# Ad8232_placa_V3_SPlanoTerra.net
KiCad netlist of a schematic drawn in EAGLE
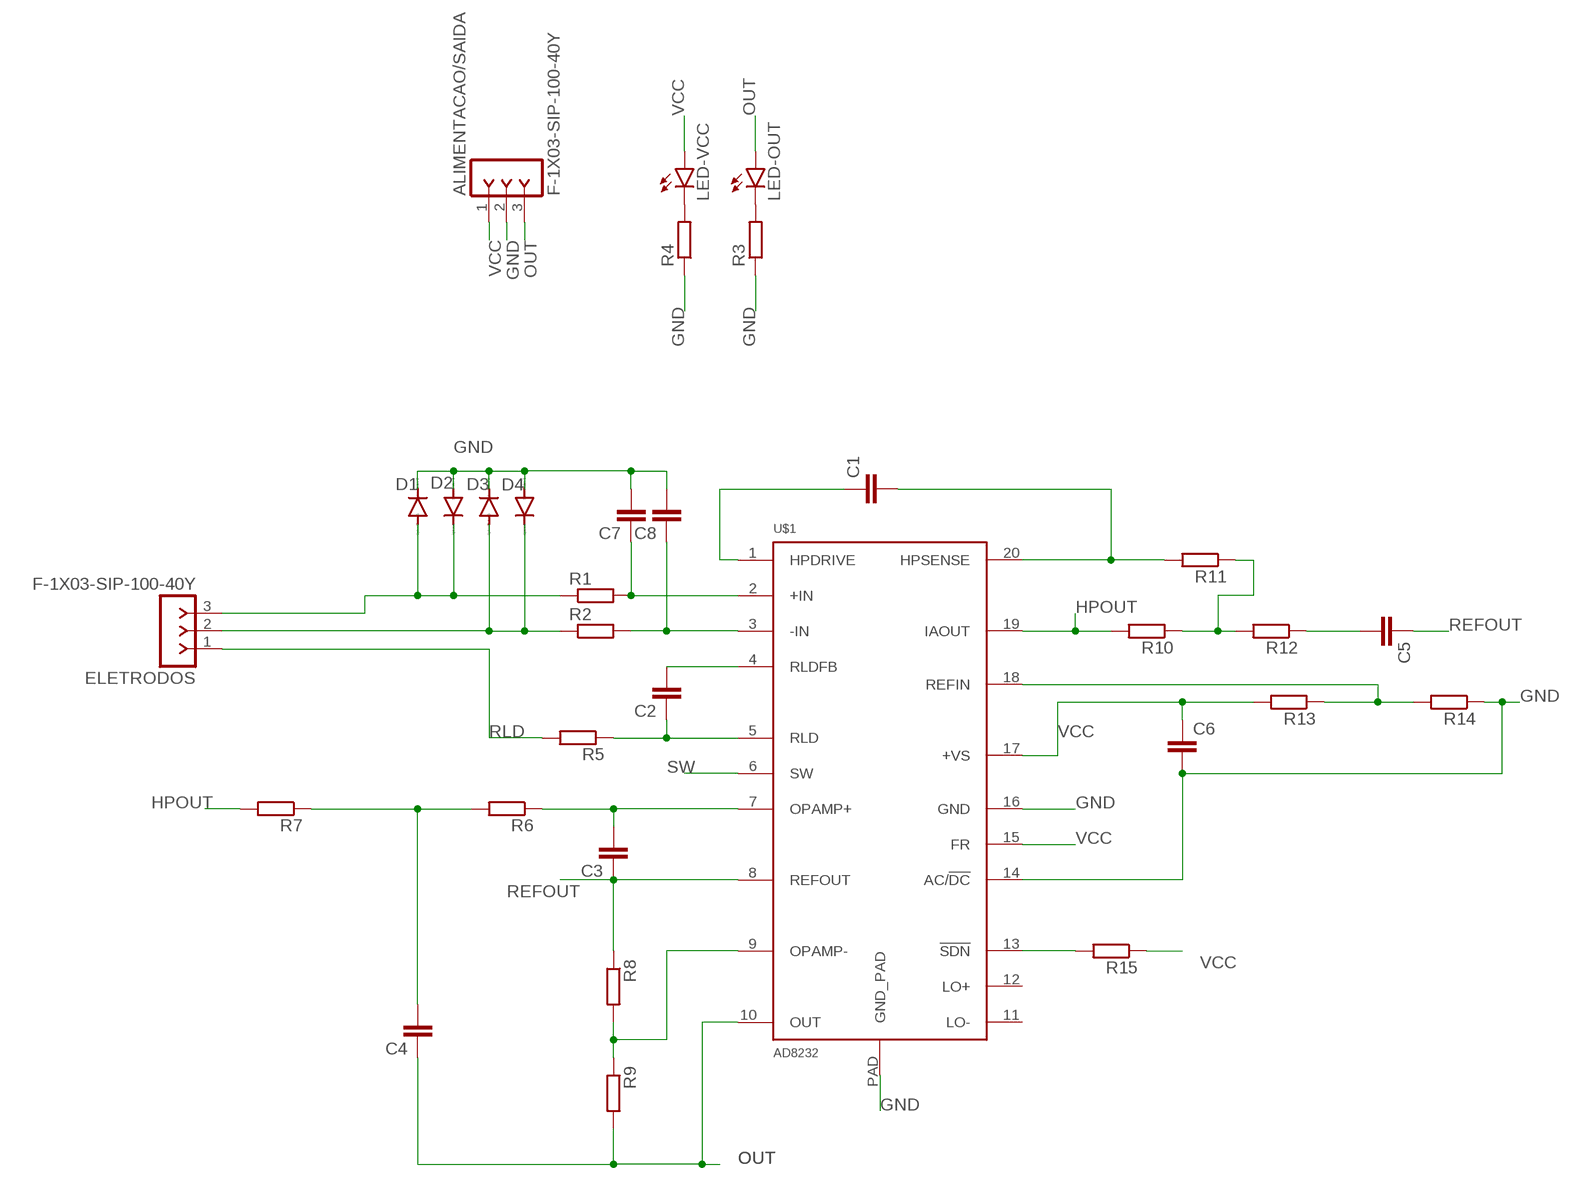
[diagram p0: schematic, sheet 1]

(export (version "E")
  (design (tool "Eeschema 10.0.6"))
  (components
    (comp (ref "ALIMENTACAO/SAIDA")
      (value "F-1X03-SIP-100-40Y")
      (footprint "eagle-import:SIP-100-03-40Y")
      (libsource (lib "eagle-import") (part "F-1X03-SIP-100-40Y"))
    )
    (comp (ref "C1")
      (value "C-EUC0805")
      (footprint "eagle-import:C0805")
      (libsource (lib "eagle-import") (part "C-EUC0805"))
    )
    (comp (ref "C2")
      (value "C-EUC0805")
      (footprint "eagle-import:C0805")
      (libsource (lib "eagle-import") (part "C-EUC0805"))
    )
    (comp (ref "C3")
      (value "C-EUC0805")
      (footprint "eagle-import:C0805")
      (libsource (lib "eagle-import") (part "C-EUC0805"))
    )
    (comp (ref "C4")
      (value "C-EUC0805")
      (footprint "eagle-import:C0805")
      (libsource (lib "eagle-import") (part "C-EUC0805"))
    )
    (comp (ref "C5")
      (value "C-EUC0805")
      (footprint "eagle-import:C0805")
      (libsource (lib "eagle-import") (part "C-EUC0805"))
    )
    (comp (ref "C6")
      (value "C-EUC0805")
      (footprint "eagle-import:C0805")
      (libsource (lib "eagle-import") (part "C-EUC0805"))
    )
    (comp (ref "C7")
      (value "C-EUC0805")
      (footprint "eagle-import:C0805")
      (libsource (lib "eagle-import") (part "C-EUC0805"))
    )
    (comp (ref "C8")
      (value "C-EUC0805")
      (footprint "eagle-import:C0805")
      (libsource (lib "eagle-import") (part "C-EUC0805"))
    )
    (comp (ref "D1")
      (value "DIODE-MINIMELF")
      (footprint "eagle-import:MINIMELF")
      (libsource (lib "eagle-import") (part "DIODE-MINIMELF"))
    )
    (comp (ref "D2")
      (value "DIODE-MINIMELF")
      (footprint "eagle-import:MINIMELF")
      (libsource (lib "eagle-import") (part "DIODE-MINIMELF"))
    )
    (comp (ref "D3")
      (value "DIODE-MINIMELF")
      (footprint "eagle-import:MINIMELF")
      (libsource (lib "eagle-import") (part "DIODE-MINIMELF"))
    )
    (comp (ref "D4")
      (value "DIODE-MINIMELF")
      (footprint "eagle-import:MINIMELF")
      (libsource (lib "eagle-import") (part "DIODE-MINIMELF"))
    )
    (comp (ref "ELETRODOS")
      (value "F-1X03-SIP-100-40Y")
      (footprint "eagle-import:SIP-100-03-40Y")
      (libsource (lib "eagle-import") (part "F-1X03-SIP-100-40Y"))
    )
    (comp (ref "LED-OUT")
      (value "LEDCHIPLED_0603")
      (footprint "eagle-import:CHIPLED_0603")
      (libsource (lib "eagle-import") (part "LEDCHIPLED_0603"))
    )
    (comp (ref "LED-VCC")
      (value "LEDCHIPLED_0603")
      (footprint "eagle-import:CHIPLED_0603")
      (libsource (lib "eagle-import") (part "LEDCHIPLED_0603"))
    )
    (comp (ref "R1")
      (value "R-EU_R0805")
      (footprint "eagle-import:R0805")
      (libsource (lib "eagle-import") (part "R-EU_R0805"))
    )
    (comp (ref "R2")
      (value "R-EU_R0805")
      (footprint "eagle-import:R0805")
      (libsource (lib "eagle-import") (part "R-EU_R0805"))
    )
    (comp (ref "R3")
      (value "R-EU_R0805")
      (footprint "eagle-import:R0805")
      (libsource (lib "eagle-import") (part "R-EU_R0805"))
    )
    (comp (ref "R4")
      (value "R-EU_R0805")
      (footprint "eagle-import:R0805")
      (libsource (lib "eagle-import") (part "R-EU_R0805"))
    )
    (comp (ref "R5")
      (value "R-EU_R0805")
      (footprint "eagle-import:R0805")
      (libsource (lib "eagle-import") (part "R-EU_R0805"))
    )
    (comp (ref "R6")
      (value "R-EU_R0805")
      (footprint "eagle-import:R0805")
      (libsource (lib "eagle-import") (part "R-EU_R0805"))
    )
    (comp (ref "R7")
      (value "R-EU_R0805")
      (footprint "eagle-import:R0805")
      (libsource (lib "eagle-import") (part "R-EU_R0805"))
    )
    (comp (ref "R8")
      (value "R-EU_R0805")
      (footprint "eagle-import:R0805")
      (libsource (lib "eagle-import") (part "R-EU_R0805"))
    )
    (comp (ref "R9")
      (value "R-EU_R0805")
      (footprint "eagle-import:R0805")
      (libsource (lib "eagle-import") (part "R-EU_R0805"))
    )
    (comp (ref "R10")
      (value "R-EU_R0805")
      (footprint "eagle-import:R0805")
      (libsource (lib "eagle-import") (part "R-EU_R0805"))
    )
    (comp (ref "R11")
      (value "R-EU_R0805")
      (footprint "eagle-import:R0805")
      (libsource (lib "eagle-import") (part "R-EU_R0805"))
    )
    (comp (ref "R12")
      (value "R-EU_R0805")
      (footprint "eagle-import:R0805")
      (libsource (lib "eagle-import") (part "R-EU_R0805"))
    )
    (comp (ref "R13")
      (value "R-EU_R0805")
      (footprint "eagle-import:R0805")
      (libsource (lib "eagle-import") (part "R-EU_R0805"))
    )
    (comp (ref "R14")
      (value "R-EU_R0805")
      (footprint "eagle-import:R0805")
      (libsource (lib "eagle-import") (part "R-EU_R0805"))
    )
    (comp (ref "R15")
      (value "R-EU_R0805")
      (footprint "eagle-import:R0805")
      (libsource (lib "eagle-import") (part "R-EU_R0805"))
    )
    (comp (ref "U$1")
      (value "AD8232")
      (footprint "eagle-import:LFCSP_20")
      (fields (field (name "MF") "Analog Devices"))
      (libsource (lib "eagle-import") (part "AD8232"))
    )
  )
  (nets
    (net (code "1") (name "/GND") (class "Default")
      (node (ref "ALIMENTACAO/SAIDA") (pin "2") (pinfunction "2_2") (pintype "passive"))
      (node (ref "C6") (pin "2") (pinfunction "2_2") (pintype "passive"))
      (node (ref "C7") (pin "2") (pinfunction "2_2") (pintype "passive"))
      (node (ref "C8") (pin "2") (pinfunction "2_2") (pintype "passive"))
      (node (ref "D1") (pin "C") (pinfunction "C_C") (pintype "passive"))
      (node (ref "D2") (pin "A") (pinfunction "A_A") (pintype "passive"))
      (node (ref "D3") (pin "C") (pinfunction "C_C") (pintype "passive"))
      (node (ref "D4") (pin "A") (pinfunction "A_A") (pintype "passive"))
      (node (ref "R14") (pin "1") (pinfunction "1_1") (pintype "passive"))
      (node (ref "R3") (pin "1") (pinfunction "1_1") (pintype "passive"))
      (node (ref "R4") (pin "1") (pinfunction "1_1") (pintype "passive"))
      (node (ref "U$1") (pin "14") (pinfunction "AC/~{DC}_14") (pintype "bidirectional"))
      (node (ref "U$1") (pin "16") (pinfunction "GND_16") (pintype "bidirectional"))
      (node (ref "U$1") (pin "PAD") (pinfunction "GND_PAD_PAD") (pintype "bidirectional"))
    )
    (net (code "2") (name "/HPOUT") (class "Default")
      (node (ref "R10") (pin "2") (pinfunction "2_2") (pintype "passive"))
      (node (ref "R7") (pin "2") (pinfunction "2_2") (pintype "passive"))
      (node (ref "U$1") (pin "19") (pinfunction "IAOUT_19") (pintype "bidirectional"))
    )
    (net (code "3") (name "/OUT") (class "Default")
      (node (ref "ALIMENTACAO/SAIDA") (pin "3") (pinfunction "3_3") (pintype "passive"))
      (node (ref "C4") (pin "1") (pinfunction "1_1") (pintype "passive"))
      (node (ref "LED-OUT") (pin "A") (pinfunction "A_A") (pintype "passive"))
      (node (ref "R9") (pin "2") (pinfunction "2_2") (pintype "passive"))
      (node (ref "U$1") (pin "10") (pinfunction "OUT_10") (pintype "bidirectional"))
    )
    (net (code "4") (name "/REFOUT") (class "Default")
      (node (ref "C3") (pin "1") (pinfunction "1_1") (pintype "passive"))
      (node (ref "C5") (pin "1") (pinfunction "1_1") (pintype "passive"))
      (node (ref "R8") (pin "1") (pinfunction "1_1") (pintype "passive"))
      (node (ref "U$1") (pin "8") (pinfunction "REFOUT_8") (pintype "bidirectional"))
    )
    (net (code "5") (name "/RLD") (class "Default")
      (node (ref "ELETRODOS") (pin "1") (pinfunction "1_1") (pintype "passive"))
      (node (ref "R5") (pin "2") (pinfunction "2_2") (pintype "passive"))
    )
    (net (code "6") (name "/SW") (class "Default")
      (node (ref "C5") (pin "2") (pinfunction "2_2") (pintype "passive"))
      (node (ref "R12") (pin "1") (pinfunction "1_1") (pintype "passive"))
      (node (ref "U$1") (pin "6") (pinfunction "SW_6") (pintype "bidirectional"))
    )
    (net (code "7") (name "/VCC") (class "Default")
      (node (ref "ALIMENTACAO/SAIDA") (pin "1") (pinfunction "1_1") (pintype "passive"))
      (node (ref "C6") (pin "1") (pinfunction "1_1") (pintype "passive"))
      (node (ref "LED-VCC") (pin "A") (pinfunction "A_A") (pintype "passive"))
      (node (ref "R13") (pin "2") (pinfunction "2_2") (pintype "passive"))
      (node (ref "R15") (pin "1") (pinfunction "1_1") (pintype "passive"))
      (node (ref "U$1") (pin "15") (pinfunction "FR_15") (pintype "bidirectional"))
      (node (ref "U$1") (pin "17") (pinfunction "+VS_17") (pintype "bidirectional"))
    )
    (net (code "8") (name "Net-(C4-Pad2)") (class "Default")
      (node (ref "C4") (pin "2") (pinfunction "2_2") (pintype "passive"))
      (node (ref "R6") (pin "2") (pinfunction "2_2") (pintype "passive"))
      (node (ref "R7") (pin "1") (pinfunction "1_1") (pintype "passive"))
    )
    (net (code "9") (name "Net-(D1-PadA)") (class "Default")
      (node (ref "D1") (pin "A") (pinfunction "A_A") (pintype "passive"))
      (node (ref "D2") (pin "C") (pinfunction "C_C") (pintype "passive"))
      (node (ref "ELETRODOS") (pin "3") (pinfunction "3_3") (pintype "passive"))
      (node (ref "R1") (pin "1") (pinfunction "1_1") (pintype "passive"))
    )
    (net (code "10") (name "Net-(D3-PadA)") (class "Default")
      (node (ref "D3") (pin "A") (pinfunction "A_A") (pintype "passive"))
      (node (ref "D4") (pin "C") (pinfunction "C_C") (pintype "passive"))
      (node (ref "ELETRODOS") (pin "2") (pinfunction "2_2") (pintype "passive"))
      (node (ref "R2") (pin "1") (pinfunction "1_1") (pintype "passive"))
    )
    (net (code "11") (name "Net-(LED-OUT-PadC)") (class "Default")
      (node (ref "LED-OUT") (pin "C") (pinfunction "C_C") (pintype "passive"))
      (node (ref "R3") (pin "2") (pinfunction "2_2") (pintype "passive"))
    )
    (net (code "12") (name "Net-(LED-VCC-PadC)") (class "Default")
      (node (ref "LED-VCC") (pin "C") (pinfunction "C_C") (pintype "passive"))
      (node (ref "R4") (pin "2") (pinfunction "2_2") (pintype "passive"))
    )
    (net (code "13") (name "Net-(R10-Pad1)") (class "Default")
      (node (ref "R10") (pin "1") (pinfunction "1_1") (pintype "passive"))
      (node (ref "R11") (pin "1") (pinfunction "1_1") (pintype "passive"))
      (node (ref "R12") (pin "2") (pinfunction "2_2") (pintype "passive"))
    )
    (net (code "14") (name "Net-(U$1-+IN)") (class "Default")
      (node (ref "C7") (pin "1") (pinfunction "1_1") (pintype "passive"))
      (node (ref "R1") (pin "2") (pinfunction "2_2") (pintype "passive"))
      (node (ref "U$1") (pin "2") (pinfunction "+IN_2") (pintype "bidirectional"))
    )
    (net (code "15") (name "Net-(U$1--IN)") (class "Default")
      (node (ref "C8") (pin "1") (pinfunction "1_1") (pintype "passive"))
      (node (ref "R2") (pin "2") (pinfunction "2_2") (pintype "passive"))
      (node (ref "U$1") (pin "3") (pinfunction "-IN_3") (pintype "bidirectional"))
    )
    (net (code "16") (name "Net-(U$1-HPDRIVE)") (class "Default")
      (node (ref "C1") (pin "1") (pinfunction "1_1") (pintype "passive"))
      (node (ref "U$1") (pin "1") (pinfunction "HPDRIVE_1") (pintype "bidirectional"))
    )
    (net (code "17") (name "Net-(U$1-HPSENSE)") (class "Default")
      (node (ref "C1") (pin "2") (pinfunction "2_2") (pintype "passive"))
      (node (ref "R11") (pin "2") (pinfunction "2_2") (pintype "passive"))
      (node (ref "U$1") (pin "20") (pinfunction "HPSENSE_20") (pintype "bidirectional"))
    )
    (net (code "18") (name "Net-(U$1-OPAMP+)") (class "Default")
      (node (ref "C3") (pin "2") (pinfunction "2_2") (pintype "passive"))
      (node (ref "R6") (pin "1") (pinfunction "1_1") (pintype "passive"))
      (node (ref "U$1") (pin "7") (pinfunction "OPAMP+_7") (pintype "bidirectional"))
    )
    (net (code "19") (name "Net-(U$1-OPAMP-)") (class "Default")
      (node (ref "R8") (pin "2") (pinfunction "2_2") (pintype "passive"))
      (node (ref "R9") (pin "1") (pinfunction "1_1") (pintype "passive"))
      (node (ref "U$1") (pin "9") (pinfunction "OPAMP-_9") (pintype "bidirectional"))
    )
    (net (code "20") (name "Net-(U$1-REFIN)") (class "Default")
      (node (ref "R13") (pin "1") (pinfunction "1_1") (pintype "passive"))
      (node (ref "R14") (pin "2") (pinfunction "2_2") (pintype "passive"))
      (node (ref "U$1") (pin "18") (pinfunction "REFIN_18") (pintype "bidirectional"))
    )
    (net (code "21") (name "Net-(U$1-RLD)") (class "Default")
      (node (ref "C2") (pin "1") (pinfunction "1_1") (pintype "passive"))
      (node (ref "R5") (pin "1") (pinfunction "1_1") (pintype "passive"))
      (node (ref "U$1") (pin "5") (pinfunction "RLD_5") (pintype "bidirectional"))
    )
    (net (code "22") (name "Net-(U$1-RLDFB)") (class "Default")
      (node (ref "C2") (pin "2") (pinfunction "2_2") (pintype "passive"))
      (node (ref "U$1") (pin "4") (pinfunction "RLDFB_4") (pintype "bidirectional"))
    )
    (net (code "23") (name "Net-(U$1-~{SDN})") (class "Default")
      (node (ref "R15") (pin "2") (pinfunction "2_2") (pintype "passive"))
      (node (ref "U$1") (pin "13") (pinfunction "~{SDN}_13") (pintype "bidirectional"))
    )
    (net (code "24") (name "unconnected-(U$1-LO+-Pad12)") (class "Default")
      (node (ref "U$1") (pin "12") (pinfunction "LO+_12") (pintype "bidirectional"))
    )
    (net (code "25") (name "unconnected-(U$1-LO--Pad11)") (class "Default")
      (node (ref "U$1") (pin "11") (pinfunction "LO-_11") (pintype "bidirectional"))
    )
  )
)
